# LcsNodes-Main-Controller-Board-A_02_04.net
KiCad netlist of a schematic drawn in EasyEDA
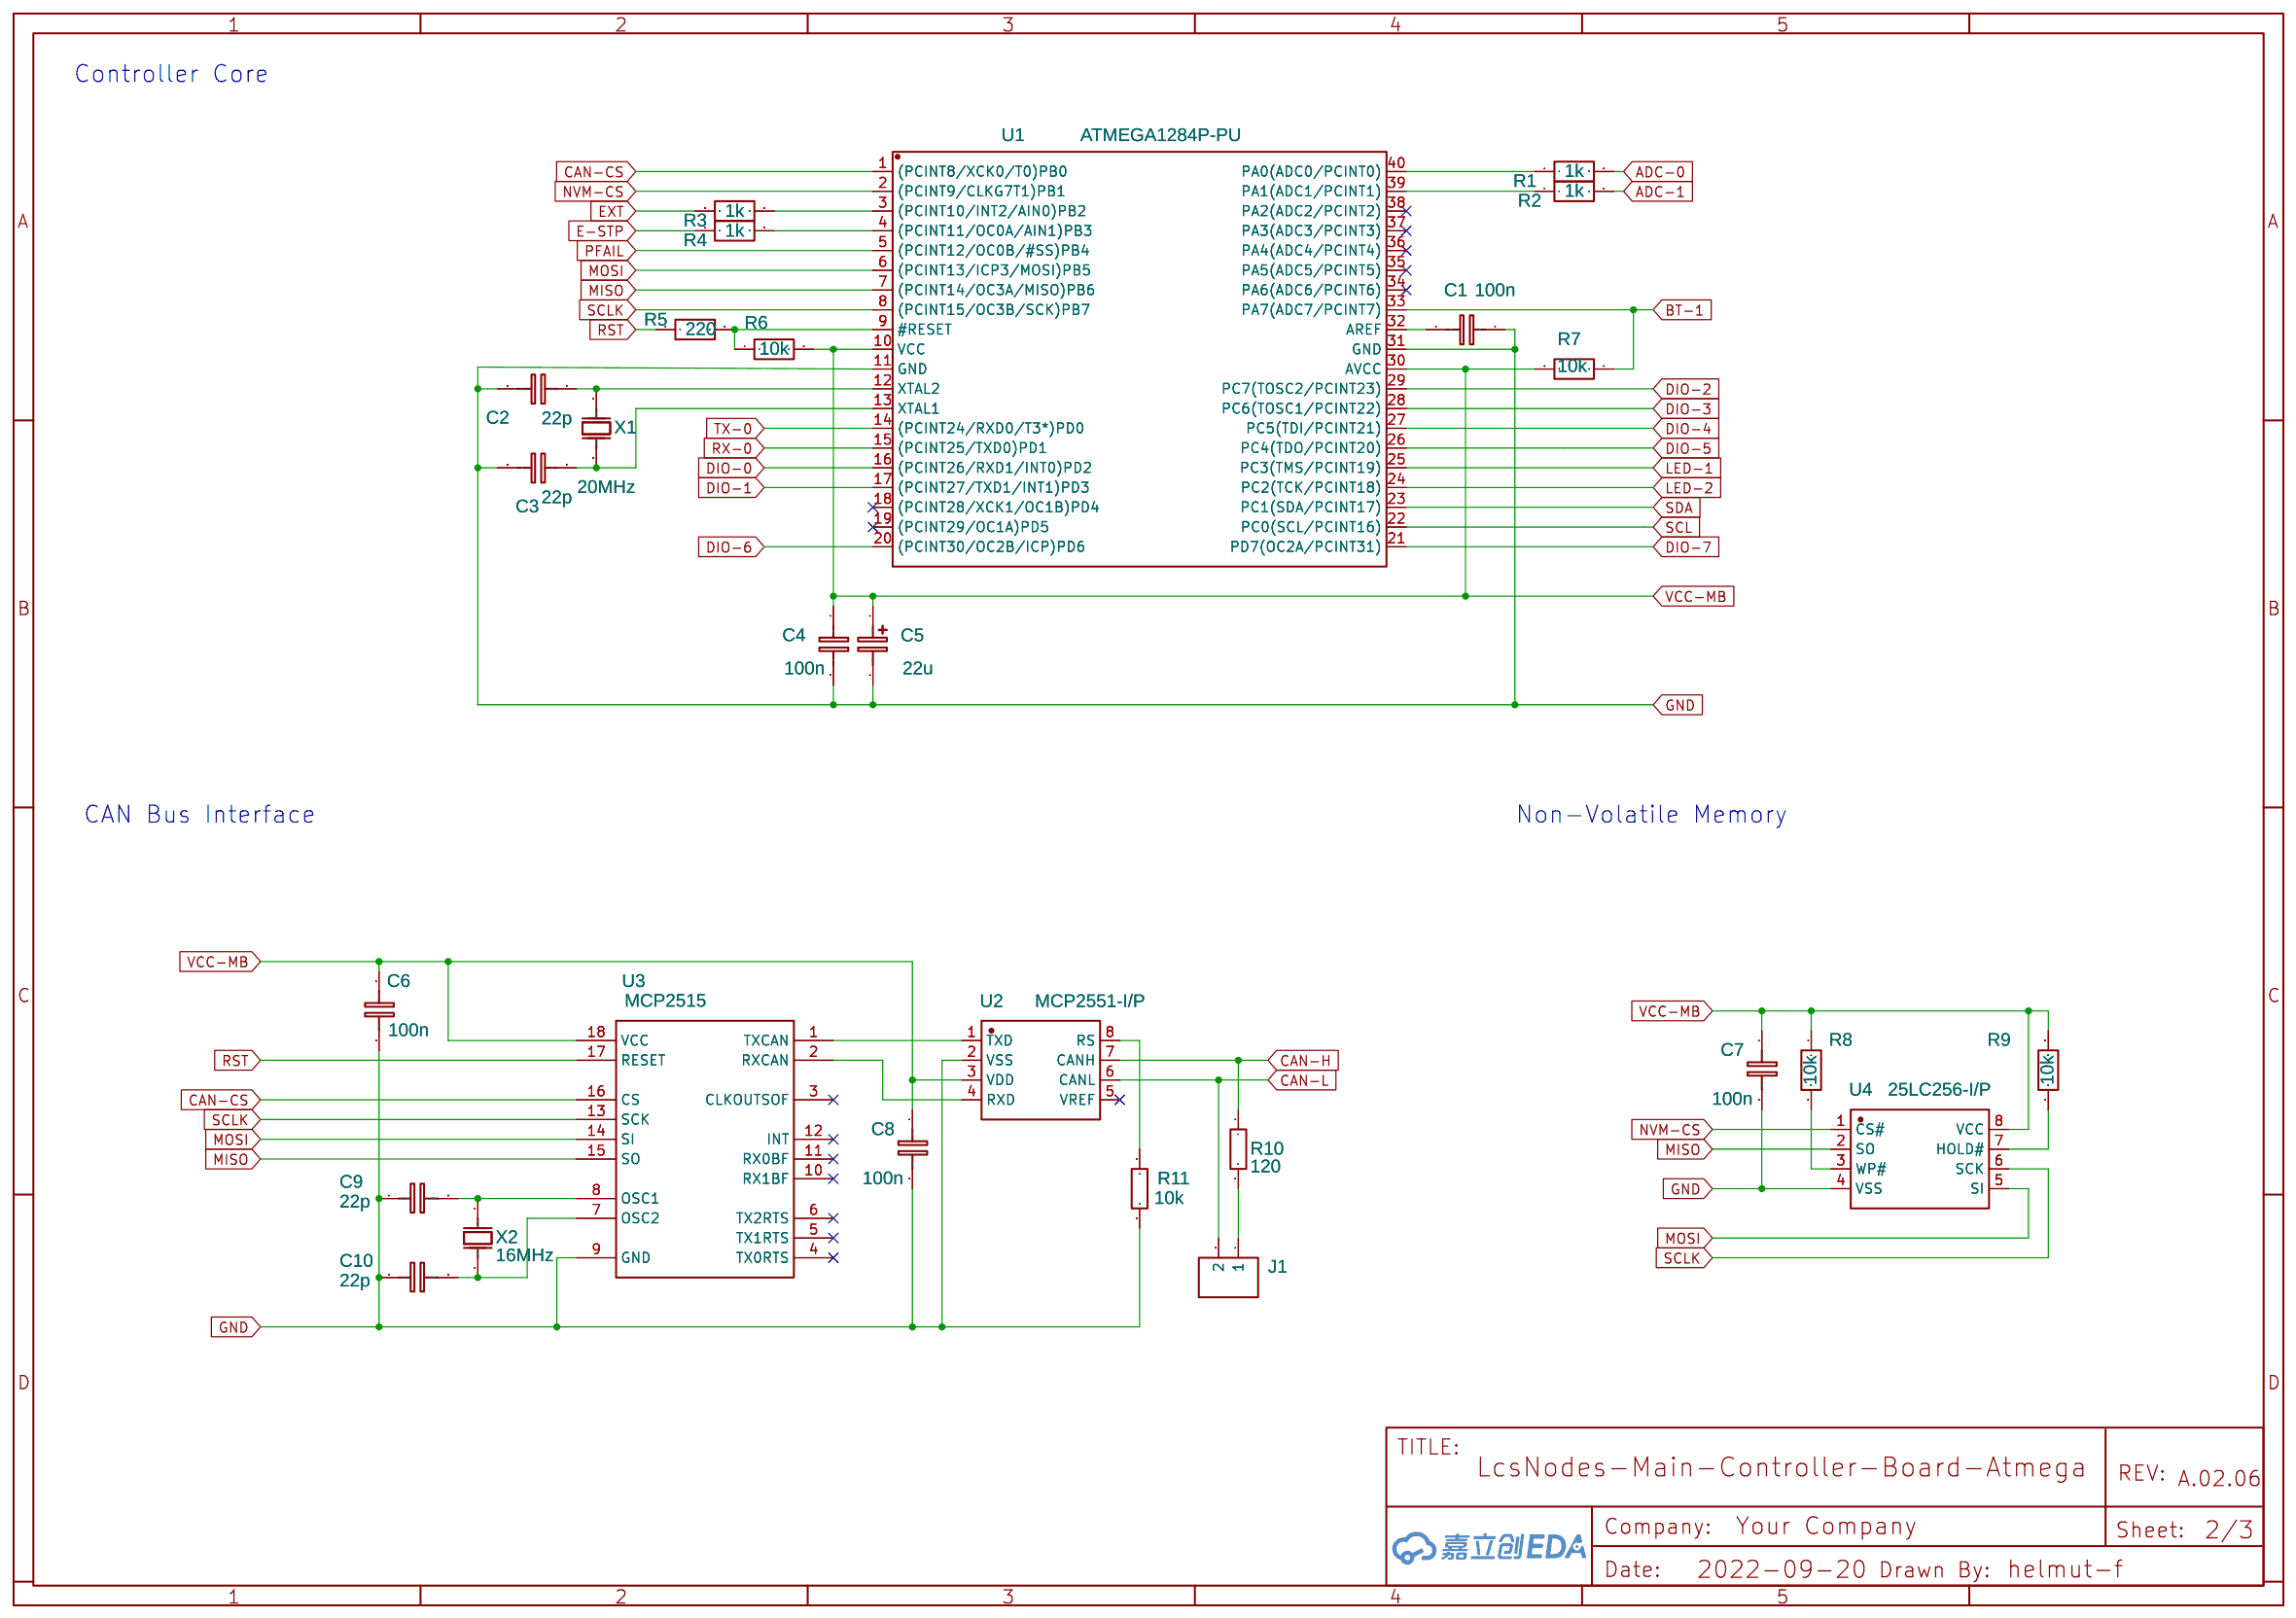
[diagram p0: Controller, CAN, NVM]
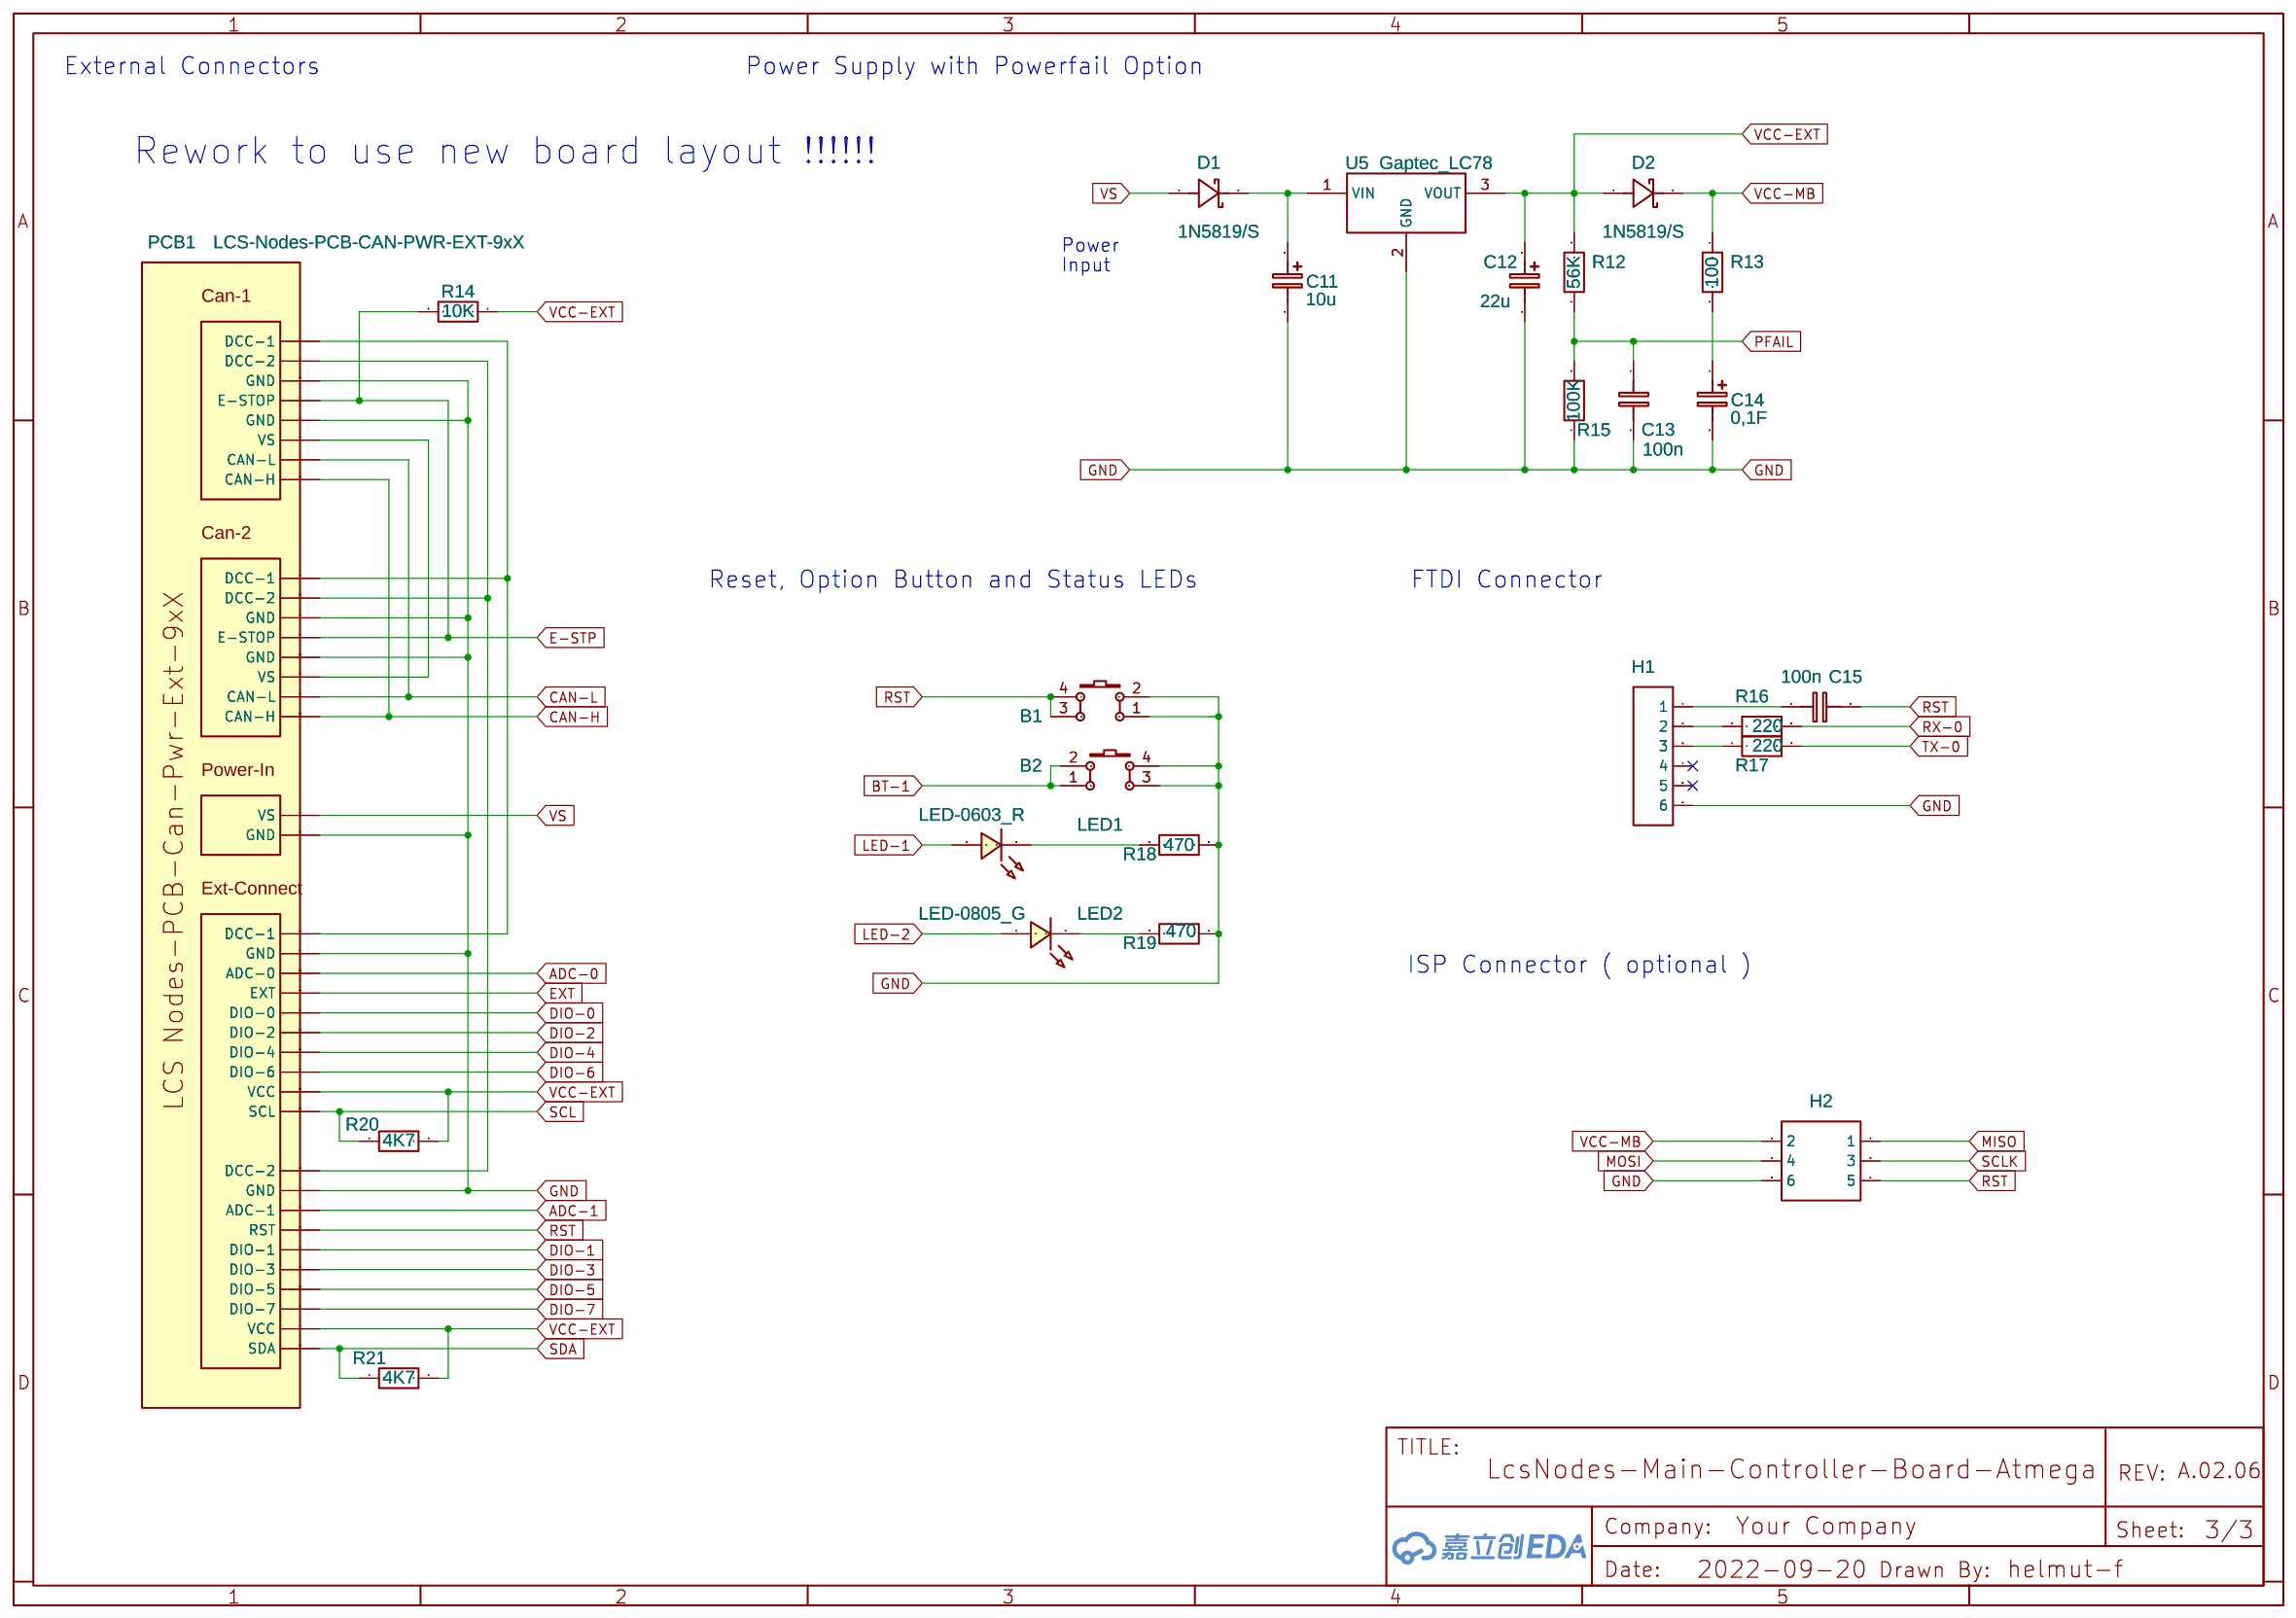
[diagram p1: Connector LCS, FTDI, ISP, Power Supply]
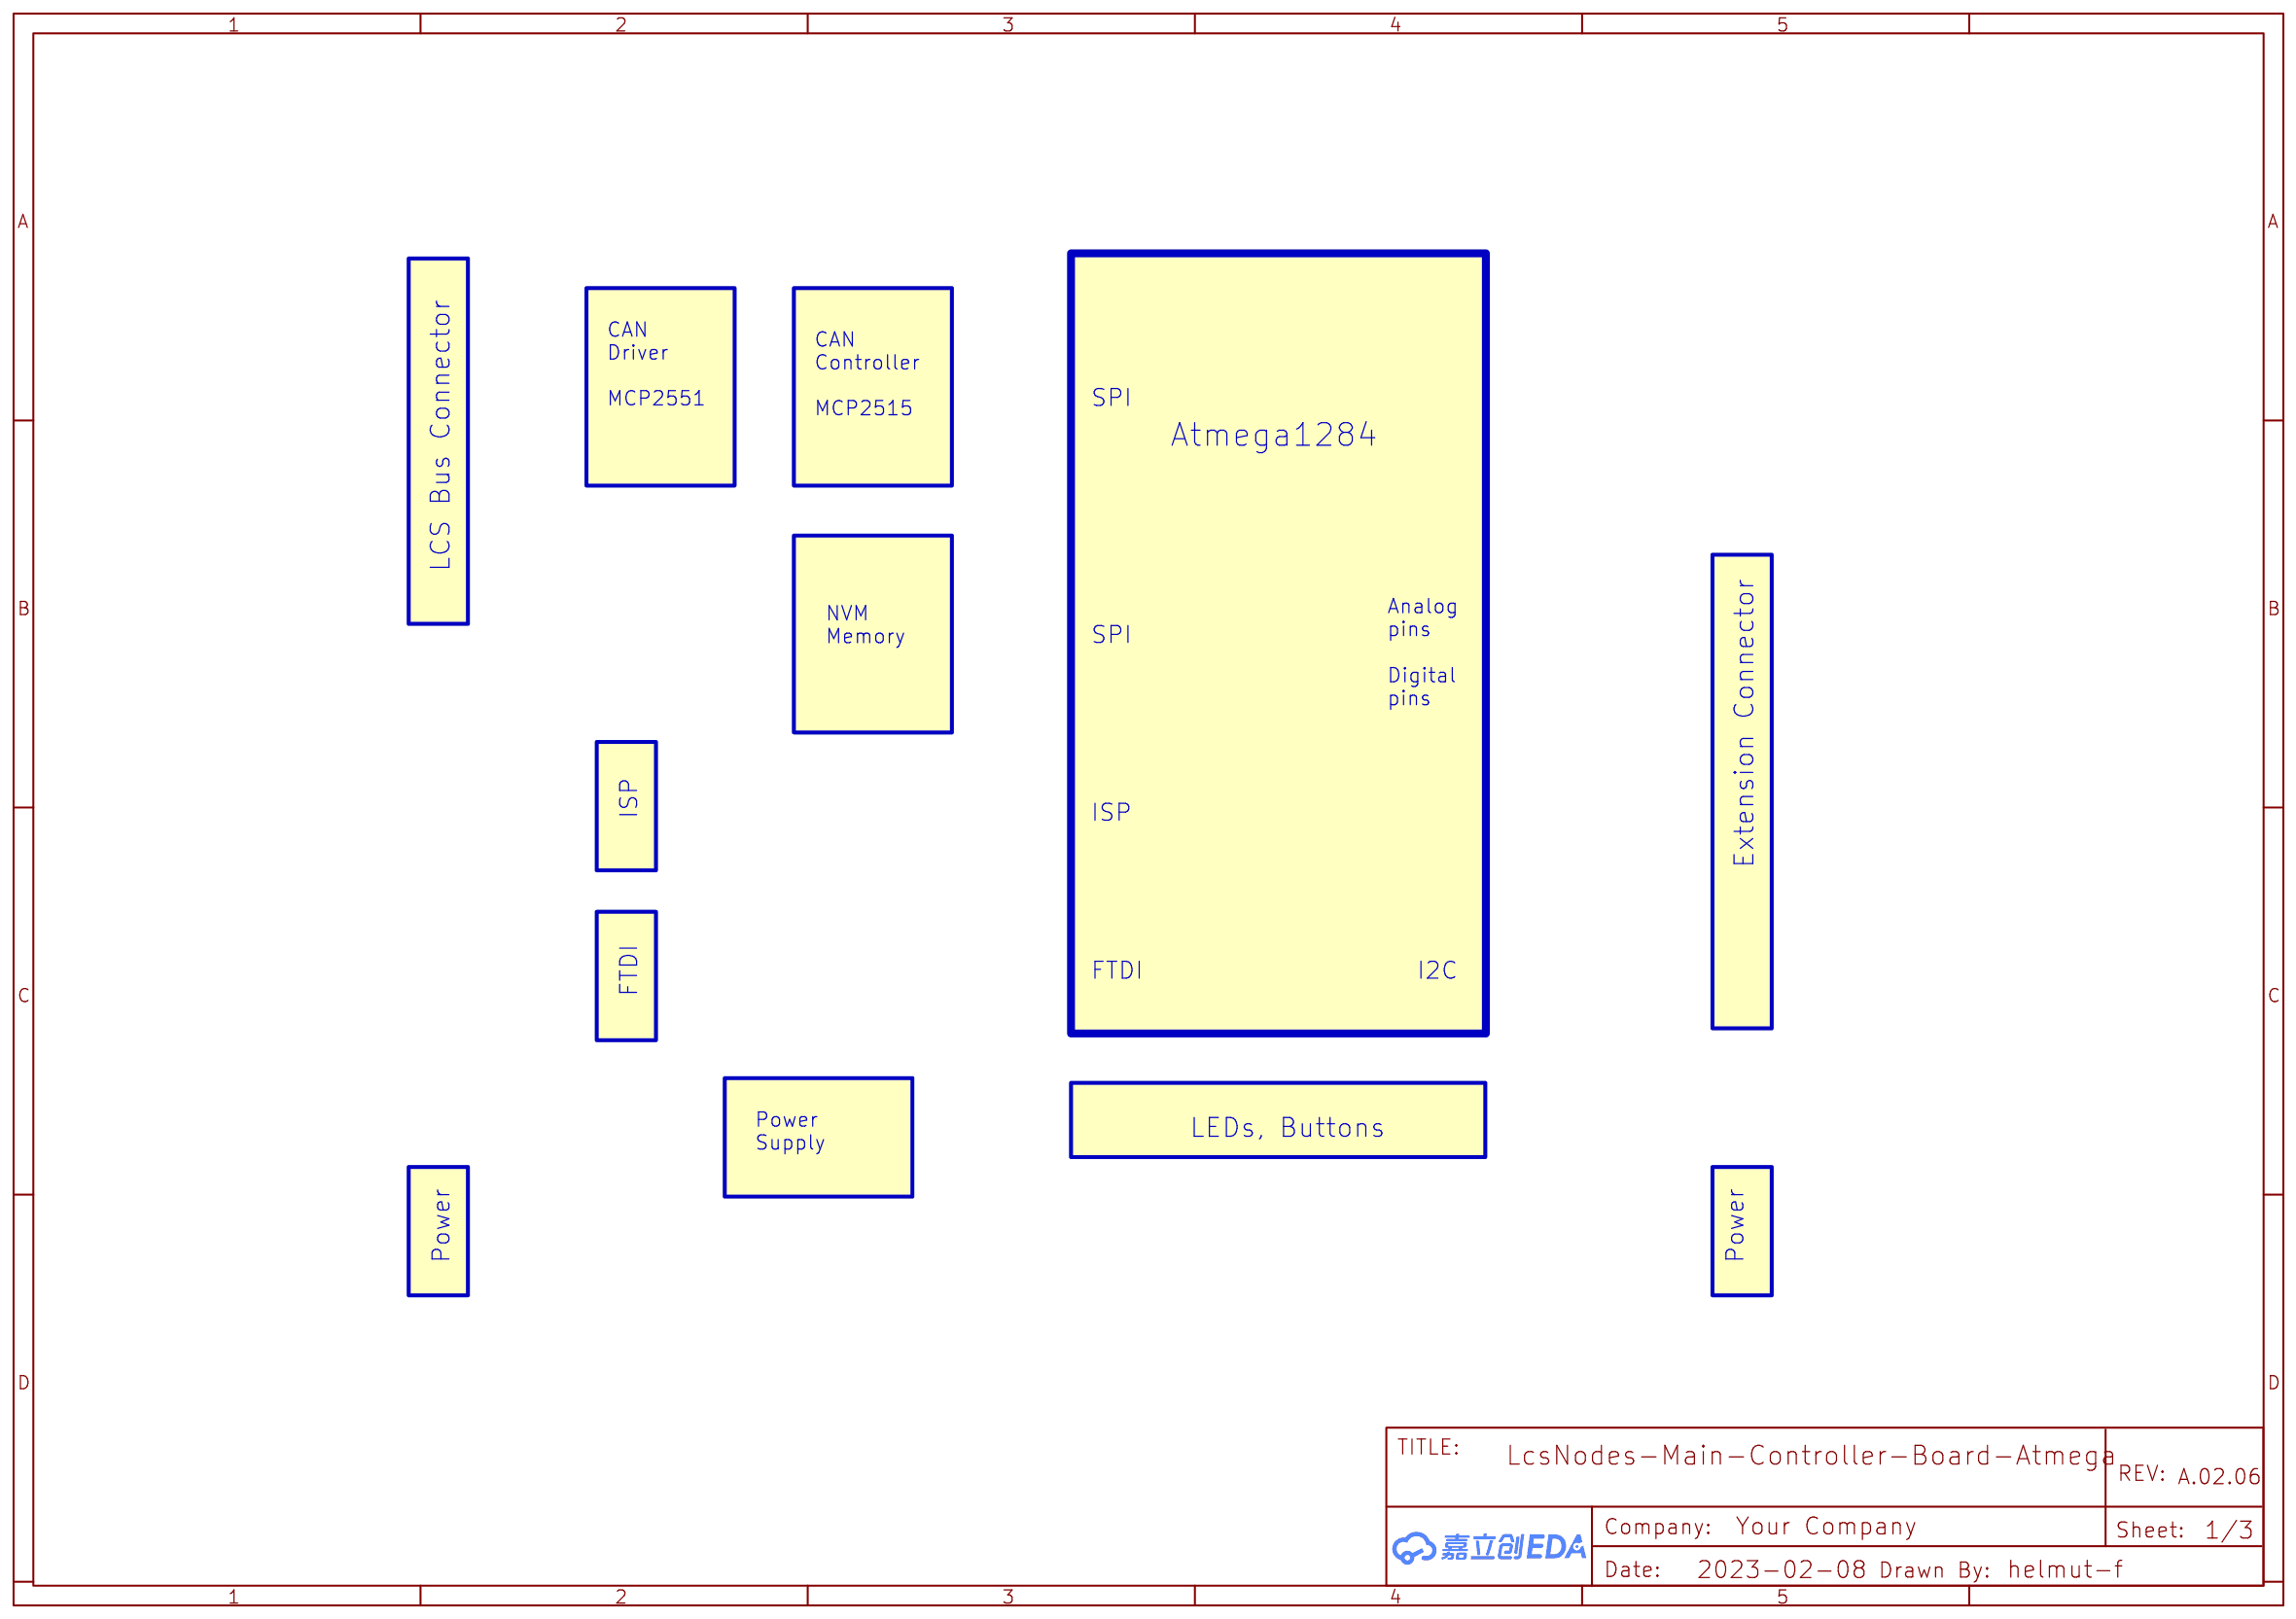
[diagram p2: Block Diagram]

(export (version "E")
  (design (tool "Eeschema 10.0.6"))
  (components
    (comp (ref "C1") (value "100n") (libsource (lib "") (part "C_RAD-0.1_EU")))
    (comp (ref "C2") (value "22p") (libsource (lib "") (part "C_0603_EU_2")))
    (comp (ref "C3") (value "22p") (libsource (lib "") (part "C_0603_EU_2")))
    (comp (ref "C4") (value "100n") (libsource (lib "") (part "C_0603_EU")))
    (comp (ref "C5") (value "22u") (libsource (lib "") (part "CE_TH_D4.0×F1.5_EU")))
    (comp (ref "C6") (value "100n") (libsource (lib "") (part "C_0603_EU")))
    (comp (ref "C7") (value "100n") (libsource (lib "") (part "C_0603_EU_1")))
    (comp (ref "C8") (value "100n") (libsource (lib "") (part "C_0603_EU")))
    (comp (ref "C9") (value "22p") (libsource (lib "") (part "C_0603_EU_3")))
    (comp (ref "C10") (value "22p") (libsource (lib "") (part "C_0603_EU_3")))
    (comp (ref "J1")
      (value "HDR-M-2.54_1x2")
      (fields (field (name "BOM_Supplier Part") "C124375"))
      (libsource (lib "") (part "HDR-M-2.54_1x2"))
    )
    (comp (ref "R1") (value "1k") (libsource (lib "") (part "R_AXIAL-0.3_EU_1")))
    (comp (ref "R2") (value "1k") (libsource (lib "") (part "R_AXIAL-0.3_EU_1")))
    (comp (ref "R3") (value "1k") (libsource (lib "") (part "R_AXIAL-0.3_EU_1")))
    (comp (ref "R4") (value "1k") (libsource (lib "") (part "R_AXIAL-0.3_EU_1")))
    (comp (ref "R5") (value "220") (libsource (lib "") (part "R_AXIAL-0.3_EU_1")))
    (comp (ref "R6") (value "10k") (libsource (lib "") (part "R_AXIAL-0.3_EU_1")))
    (comp (ref "R7") (value "10k") (libsource (lib "") (part "R_AXIAL-0.3_EU")))
    (comp (ref "R8") (value "10k") (libsource (lib "") (part "R_AXIAL-0.3_EU_3")))
    (comp (ref "R9") (value "10k") (libsource (lib "") (part "R_AXIAL-0.3_EU_2")))
    (comp (ref "R10") (value "120") (libsource (lib "") (part "RESISTOR-AXIAL-0.1")))
    (comp (ref "R11") (value "10k") (libsource (lib "") (part "RESISTOR-AXIAL-0.1")))
    (comp (ref "U1")
      (value "ATMEGA1284P-PU")
      (fields (field (name "BOM_Supplier Part") "C116839"))
      (libsource (lib "") (part "ATMEGA1284P-PU"))
    )
    (comp (ref "U2")
      (value "MCP2551-I/P")
      (fields (field (name "BOM_Supplier Part") "C411627"))
      (libsource (lib "") (part "MCP2551-I/P"))
    )
    (comp (ref "U3") (value "MCP2515") (libsource (lib "") (part "MCP2515")))
    (comp (ref "U4")
      (value "25LC256-I/P")
      (fields (field (name "BOM_Supplier Part") "C511271"))
      (libsource (lib "") (part "25LC256-I/P"))
    )
    (comp (ref "X1")
      (value "20MHz")
      (fields
        (field (name "BOM_Manufacturer Part") "X49SM16MSD2SI")
        (field (name "BOM_Supplier Part") "C90678")
      )
      (libsource (lib "") (part "X49SM16MSD2SI"))
    )
    (comp (ref "X2")
      (value "16MHz")
      (fields
        (field (name "BOM_Manufacturer Part") "X49SM16MSD2SI")
        (field (name "BOM_Supplier Part") "C90678")
      )
      (libsource (lib "") (part "X49SM16MSD2SI"))
    )
    (comp (ref "B1")
      (value "Reset")
      (fields
        (field (name "BOM_Manufacturer Part") "K2-1102DP-E4SW-04")
        (field (name "BOM_Supplier Part") "C136684")
      )
      (libsource (lib "") (part "K4-6×6_TH_1"))
    )
    (comp (ref "B2")
      (value "Opt")
      (fields
        (field (name "BOM_Manufacturer Part") "K2-1102DP-E4SW-04")
        (field (name "BOM_Supplier Part") "C136684")
      )
      (libsource (lib "") (part "K4-6×6_TH"))
    )
    (comp (ref "C11") (value "10u") (libsource (lib "") (part "CE_SMD_D5.0×H5.5_EU")))
    (comp (ref "C12") (value "22u") (libsource (lib "") (part "CE_SMD_D5.0×H5.5_EU")))
    (comp (ref "C13") (value "100n") (libsource (lib "") (part "C_RAD-0.2_EU")))
    (comp (ref "C14") (value "0,1F") (libsource (lib "") (part "C_Tan_SMD_A_EU")))
    (comp (ref "C15") (value "100n") (libsource (lib "") (part "C_0603_EU")))
    (comp (ref "D1")
      (value "1N5819/S")
      (fields (field (name "BOM_Supplier Part") "C9900003833"))
      (libsource (lib "") (part "1N5819/S"))
    )
    (comp (ref "D2")
      (value "1N5819/S")
      (fields (field (name "BOM_Supplier Part") "C9900003833"))
      (libsource (lib "") (part "1N5819/S"))
    )
    (comp (ref "H1")
      (value "HDR-F-2.54_1x6")
      (fields (field (name "BOM_Supplier Part") "C40877"))
      (libsource (lib "") (part "HDR-F-2.54_1x6"))
    )
    (comp (ref "H2")
      (value "HDR-F-2.54_2x3")
      (fields (field (name "BOM_Supplier Part") "C65114"))
      (libsource (lib "") (part "HDR-F-2.54_2x3"))
    )
    (comp (ref "LED1")
      (value "LED-0603_R")
      (fields
        (field (name "BOM_Manufacturer Part") "19-217/R6C-AL1M2VY/3T")
        (field (name "BOM_Supplier Part") "C72044")
      )
      (libsource (lib "") (part "LED-0603_R"))
    )
    (comp (ref "LED2")
      (value "LED-0805_G")
      (fields (field (name "BOM_Manufacturer Part") "NCD0805G1") (field (name "BOM_Supplier Part") "C84260"))
      (libsource (lib "") (part "LED-0805_G"))
    )
    (comp (ref "PCB1")
      (value "LCS-Nodes-PCB-CAN-PWR-EXT-9xX")
      (libsource (lib "") (part "LCS-Nodes-PCB-CAN-PWR-EXT-9xX"))
    )
    (comp (ref "R12") (value "56K") (libsource (lib "") (part "R_AXIAL-0.3_EU_1")))
    (comp (ref "R13") (value "100") (libsource (lib "") (part "R_AXIAL-0.3_EU_3")))
    (comp (ref "R14") (value "10K") (libsource (lib "") (part "R_AXIAL-0.3_EU")))
    (comp (ref "R15") (value "100K") (libsource (lib "") (part "R_AXIAL-0.3_EU_1")))
    (comp (ref "R16") (value "220") (libsource (lib "") (part "R_AXIAL-0.3_EU_2")))
    (comp (ref "R17") (value "220") (libsource (lib "") (part "R_AXIAL-0.3_EU_2")))
    (comp (ref "R18") (value "470") (libsource (lib "") (part "R_0805_EU")))
    (comp (ref "R19") (value "470") (libsource (lib "") (part "R_0805_EU")))
    (comp (ref "R20") (value "4K7") (libsource (lib "") (part "R_AXIAL-0.3_EU_2")))
    (comp (ref "R21") (value "4K7") (libsource (lib "") (part "R_AXIAL-0.3_EU_2")))
    (comp (ref "U5") (value "Gaptec_LC78") (libsource (lib "") (part "Gaptec_LC78")))
  )
  (nets
    (net (code "1") (name "ADC-0") (class "Default")
      (node (ref "PCB1") (pin "32") (pinfunction "ADC-0_32") (pintype "unspecified"))
      (node (ref "R1") (pin "2") (pinfunction "2_2") (pintype "unspecified"))
    )
    (net (code "2") (name "ADC-1") (class "Default")
      (node (ref "PCB1") (pin "42") (pinfunction "ADC-1_42") (pintype "unspecified"))
      (node (ref "R2") (pin "2") (pinfunction "2_2") (pintype "unspecified"))
    )
    (net (code "3") (name "BT-1") (class "Default")
      (node (ref "B2") (pin "1") (pinfunction "1_1") (pintype "unspecified"))
      (node (ref "B2") (pin "2") (pinfunction "2_2") (pintype "unspecified"))
      (node (ref "R7") (pin "1") (pinfunction "1_1") (pintype "unspecified"))
      (node (ref "U1") (pin "33") (pinfunction "PA7(ADC7/PCINT7)_33") (pintype "unspecified"))
    )
    (net (code "4") (name "CAN-CS") (class "Default")
      (node (ref "U1") (pin "1") (pinfunction "(PCINT8/XCK0/T0)PB0_1") (pintype "unspecified"))
      (node (ref "U3") (pin "16") (pinfunction "CS_16") (pintype "unspecified"))
    )
    (net (code "5") (name "CAN-H") (class "Default")
      (node (ref "PCB1") (pin "18") (pinfunction "CAN-H_18") (pintype "unspecified"))
      (node (ref "PCB1") (pin "8") (pinfunction "CAN-H_8") (pintype "unspecified"))
      (node (ref "R10") (pin "1") (pinfunction "1_1") (pintype "input"))
      (node (ref "U2") (pin "7") (pinfunction "CANH_7") (pintype "unspecified"))
    )
    (net (code "6") (name "CAN-L") (class "Default")
      (node (ref "J1") (pin "2") (pinfunction "2_2") (pintype "unspecified"))
      (node (ref "PCB1") (pin "17") (pinfunction "CAN-L_17") (pintype "unspecified"))
      (node (ref "PCB1") (pin "7") (pinfunction "CAN-L_7") (pintype "unspecified"))
      (node (ref "U2") (pin "6") (pinfunction "CANL_6") (pintype "unspecified"))
    )
    (net (code "7") (name "DIO-0") (class "Default")
      (node (ref "PCB1") (pin "34") (pinfunction "DIO-0_34") (pintype "unspecified"))
      (node (ref "U1") (pin "16") (pinfunction "(PCINT26/RXD1/INT0)PD2_16") (pintype "unspecified"))
    )
    (net (code "8") (name "DIO-1") (class "Default")
      (node (ref "PCB1") (pin "44") (pinfunction "DIO-1_44") (pintype "unspecified"))
      (node (ref "U1") (pin "17") (pinfunction "(PCINT27/TXD1/INT1)PD3_17") (pintype "unspecified"))
    )
    (net (code "9") (name "DIO-2") (class "Default")
      (node (ref "PCB1") (pin "35") (pinfunction "DIO-2_35") (pintype "unspecified"))
      (node (ref "U1") (pin "29") (pinfunction "PC7(TOSC2/PCINT23)_29") (pintype "unspecified"))
    )
    (net (code "10") (name "DIO-3") (class "Default")
      (node (ref "PCB1") (pin "45") (pinfunction "DIO-3_45") (pintype "unspecified"))
      (node (ref "U1") (pin "28") (pinfunction "PC6(TOSC1/PCINT22)_28") (pintype "unspecified"))
    )
    (net (code "11") (name "DIO-4") (class "Default")
      (node (ref "PCB1") (pin "36") (pinfunction "DIO-4_36") (pintype "unspecified"))
      (node (ref "U1") (pin "27") (pinfunction "PC5(TDI/PCINT21)_27") (pintype "unspecified"))
    )
    (net (code "12") (name "DIO-5") (class "Default")
      (node (ref "PCB1") (pin "46") (pinfunction "DIO-5_46") (pintype "unspecified"))
      (node (ref "U1") (pin "26") (pinfunction "PC4(TDO/PCINT20)_26") (pintype "unspecified"))
    )
    (net (code "13") (name "DIO-6") (class "Default")
      (node (ref "PCB1") (pin "37") (pinfunction "DIO-6_37") (pintype "unspecified"))
      (node (ref "U1") (pin "20") (pinfunction "(PCINT30/OC2B/ICP)PD6_20") (pintype "unspecified"))
    )
    (net (code "14") (name "DIO-7") (class "Default")
      (node (ref "PCB1") (pin "47") (pinfunction "DIO-7_47") (pintype "unspecified"))
      (node (ref "U1") (pin "21") (pinfunction "PD7(OC2A/PCINT31)_21") (pintype "unspecified"))
    )
    (net (code "15") (name "E-STP") (class "Default")
      (node (ref "PCB1") (pin "14") (pinfunction "E-STOP_14") (pintype "unspecified"))
      (node (ref "PCB1") (pin "4") (pinfunction "E-STOP_4") (pintype "unspecified"))
      (node (ref "R14") (pin "2") (pinfunction "2_2") (pintype "unspecified"))
      (node (ref "R4") (pin "1") (pinfunction "1_1") (pintype "unspecified"))
    )
    (net (code "16") (name "EXT") (class "Default")
      (node (ref "PCB1") (pin "33") (pinfunction "EXT_33") (pintype "unspecified"))
      (node (ref "R3") (pin "1") (pinfunction "1_1") (pintype "unspecified"))
    )
    (net (code "17") (name "GND") (class "Default")
      (node (ref "B1") (pin "1") (pinfunction "1_1") (pintype "unspecified"))
      (node (ref "B1") (pin "2") (pinfunction "2_2") (pintype "unspecified"))
      (node (ref "B2") (pin "3") (pinfunction "3_3") (pintype "unspecified"))
      (node (ref "B2") (pin "4") (pinfunction "4_4") (pintype "unspecified"))
      (node (ref "C1") (pin "1") (pinfunction "1_1") (pintype "unspecified"))
      (node (ref "C10") (pin "1") (pinfunction "1_1") (pintype "unspecified"))
      (node (ref "C11") (pin "2") (pinfunction "2_2") (pintype "unspecified"))
      (node (ref "C12") (pin "2") (pinfunction "2_2") (pintype "unspecified"))
      (node (ref "C13") (pin "2") (pinfunction "2_2") (pintype "unspecified"))
      (node (ref "C14") (pin "2") (pinfunction "2_2") (pintype "unspecified"))
      (node (ref "C2") (pin "2") (pinfunction "2_2") (pintype "unspecified"))
      (node (ref "C3") (pin "2") (pinfunction "2_2") (pintype "unspecified"))
      (node (ref "C4") (pin "2") (pinfunction "2_2") (pintype "unspecified"))
      (node (ref "C5") (pin "2") (pinfunction "2_2") (pintype "unspecified"))
      (node (ref "C6") (pin "2") (pinfunction "2_2") (pintype "unspecified"))
      (node (ref "C7") (pin "2") (pinfunction "2_2") (pintype "unspecified"))
      (node (ref "C8") (pin "2") (pinfunction "2_2") (pintype "unspecified"))
      (node (ref "C9") (pin "1") (pinfunction "1_1") (pintype "unspecified"))
      (node (ref "H1") (pin "6") (pinfunction "6_6") (pintype "input"))
      (node (ref "H2") (pin "6") (pinfunction "6_6") (pintype "input"))
      (node (ref "PCB1") (pin "13") (pinfunction "GND_13") (pintype "unspecified"))
      (node (ref "PCB1") (pin "15") (pinfunction "GND_15") (pintype "unspecified"))
      (node (ref "PCB1") (pin "21") (pinfunction "GND_21") (pintype "unspecified"))
      (node (ref "PCB1") (pin "3") (pinfunction "GND_3") (pintype "unspecified"))
      (node (ref "PCB1") (pin "31") (pinfunction "GND_31") (pintype "unspecified"))
      (node (ref "PCB1") (pin "41") (pinfunction "GND_41") (pintype "unspecified"))
      (node (ref "PCB1") (pin "5") (pinfunction "GND_5") (pintype "unspecified"))
      (node (ref "R11") (pin "2") (pinfunction "2_2") (pintype "input"))
      (node (ref "R15") (pin "1") (pinfunction "1_1") (pintype "unspecified"))
      (node (ref "R18") (pin "1") (pinfunction "1_1") (pintype "unspecified"))
      (node (ref "R19") (pin "1") (pinfunction "1_1") (pintype "unspecified"))
      (node (ref "U1") (pin "11") (pinfunction "GND_11") (pintype "unspecified"))
      (node (ref "U1") (pin "31") (pinfunction "GND_31") (pintype "unspecified"))
      (node (ref "U2") (pin "2") (pinfunction "VSS_2") (pintype "unspecified"))
      (node (ref "U3") (pin "9") (pinfunction "GND_9") (pintype "passive"))
      (node (ref "U4") (pin "4") (pinfunction "VSS_4") (pintype "unspecified"))
      (node (ref "U5") (pin "2") (pinfunction "GND_2") (pintype "unspecified"))
    )
    (net (code "18") (name "LED-1") (class "Default")
      (node (ref "LED1") (pin "1") (pinfunction "1_1") (pintype "unspecified"))
      (node (ref "U1") (pin "25") (pinfunction "PC3(TMS/PCINT19)_25") (pintype "unspecified"))
    )
    (net (code "19") (name "LED-2") (class "Default")
      (node (ref "LED2") (pin "1") (pinfunction "1_1") (pintype "unspecified"))
      (node (ref "U1") (pin "24") (pinfunction "PC2(TCK/PCINT18)_24") (pintype "unspecified"))
    )
    (net (code "20") (name "MISO") (class "Default")
      (node (ref "H2") (pin "1") (pinfunction "1_1") (pintype "input"))
      (node (ref "U1") (pin "7") (pinfunction "(PCINT14/OC3A/MISO)PB6_7") (pintype "unspecified"))
      (node (ref "U3") (pin "15") (pinfunction "SO_15") (pintype "output"))
      (node (ref "U4") (pin "2") (pinfunction "SO_2") (pintype "unspecified"))
    )
    (net (code "21") (name "MOSI") (class "Default")
      (node (ref "H2") (pin "4") (pinfunction "4_4") (pintype "input"))
      (node (ref "U1") (pin "6") (pinfunction "(PCINT13/ICP3/MOSI)PB5_6") (pintype "unspecified"))
      (node (ref "U3") (pin "14") (pinfunction "SI_14") (pintype "unspecified"))
      (node (ref "U4") (pin "5") (pinfunction "SI_5") (pintype "unspecified"))
    )
    (net (code "22") (name "NVM-CS") (class "Default")
      (node (ref "U1") (pin "2") (pinfunction "(PCINT9/CLKG7T1)PB1_2") (pintype "unspecified"))
      (node (ref "U4") (pin "1") (pinfunction "CS#_1") (pintype "unspecified"))
    )
    (net (code "23") (name "Net-(C14-Pad1)") (class "Default")
      (node (ref "C14") (pin "1") (pinfunction "1_1") (pintype "unspecified"))
      (node (ref "R13") (pin "2") (pinfunction "2_2") (pintype "unspecified"))
    )
    (net (code "24") (name "Net-(C15-Pad1)") (class "Default")
      (node (ref "C15") (pin "1") (pinfunction "1_1") (pintype "unspecified"))
      (node (ref "H1") (pin "1") (pinfunction "1_1") (pintype "input"))
    )
    (net (code "25") (name "Net-(D1-K)") (class "Default")
      (node (ref "C11") (pin "1") (pinfunction "1_1") (pintype "unspecified"))
      (node (ref "D1") (pin "2") (pinfunction "K_2") (pintype "unspecified"))
      (node (ref "U5") (pin "1") (pinfunction "VIN_1") (pintype "unspecified"))
    )
    (net (code "26") (name "Net-(H1-Pad2)") (class "Default")
      (node (ref "H1") (pin "2") (pinfunction "2_2") (pintype "input"))
      (node (ref "R16") (pin "1") (pinfunction "1_1") (pintype "unspecified"))
    )
    (net (code "27") (name "Net-(H1-Pad3)") (class "Default")
      (node (ref "H1") (pin "3") (pinfunction "3_3") (pintype "input"))
      (node (ref "R17") (pin "1") (pinfunction "1_1") (pintype "unspecified"))
    )
    (net (code "28") (name "Net-(J1-Pad1)") (class "Default")
      (node (ref "J1") (pin "1") (pinfunction "1_1") (pintype "unspecified"))
      (node (ref "R10") (pin "2") (pinfunction "2_2") (pintype "input"))
    )
    (net (code "29") (name "Net-(LED1-Pad2)") (class "Default")
      (node (ref "LED1") (pin "2") (pinfunction "2_2") (pintype "unspecified"))
      (node (ref "R18") (pin "2") (pinfunction "2_2") (pintype "unspecified"))
    )
    (net (code "30") (name "Net-(LED2-Pad2)") (class "Default")
      (node (ref "LED2") (pin "2") (pinfunction "2_2") (pintype "unspecified"))
      (node (ref "R19") (pin "2") (pinfunction "2_2") (pintype "unspecified"))
    )
    (net (code "31") (name "Net-(PCB1-DCC-1-Pad1)") (class "Default")
      (node (ref "PCB1") (pin "1") (pinfunction "DCC-1_1") (pintype "unspecified"))
      (node (ref "PCB1") (pin "11") (pinfunction "DCC-1_11") (pintype "unspecified"))
      (node (ref "PCB1") (pin "30") (pinfunction "DCC-1_30") (pintype "unspecified"))
    )
    (net (code "32") (name "Net-(PCB1-DCC-2-Pad12)") (class "Default")
      (node (ref "PCB1") (pin "12") (pinfunction "DCC-2_12") (pintype "unspecified"))
      (node (ref "PCB1") (pin "2") (pinfunction "DCC-2_2") (pintype "unspecified"))
      (node (ref "PCB1") (pin "40") (pinfunction "DCC-2_40") (pintype "unspecified"))
    )
    (net (code "33") (name "Net-(PCB1-VS-Pad16)") (class "Default")
      (node (ref "PCB1") (pin "16") (pinfunction "VS_16") (pintype "unspecified"))
      (node (ref "PCB1") (pin "6") (pinfunction "VS_6") (pintype "unspecified"))
    )
    (net (code "34") (name "Net-(U1-#RESET)") (class "Default")
      (node (ref "R5") (pin "2") (pinfunction "2_2") (pintype "unspecified"))
      (node (ref "R6") (pin "1") (pinfunction "1_1") (pintype "unspecified"))
      (node (ref "U1") (pin "9") (pinfunction "#RESET_9") (pintype "unspecified"))
    )
    (net (code "35") (name "Net-(U1-(PCINT10{slash}INT2{slash}AIN0)PB2)") (class "Default")
      (node (ref "R3") (pin "2") (pinfunction "2_2") (pintype "unspecified"))
      (node (ref "U1") (pin "3") (pinfunction "(PCINT10/INT2/AIN0)PB2_3") (pintype "unspecified"))
    )
    (net (code "36") (name "Net-(U1-(PCINT11{slash}OC0A{slash}AIN1)PB3)") (class "Default")
      (node (ref "R4") (pin "2") (pinfunction "2_2") (pintype "unspecified"))
      (node (ref "U1") (pin "4") (pinfunction "(PCINT11/OC0A/AIN1)PB3_4") (pintype "unspecified"))
    )
    (net (code "37") (name "Net-(U1-AREF)") (class "Default")
      (node (ref "C1") (pin "2") (pinfunction "2_2") (pintype "unspecified"))
      (node (ref "U1") (pin "32") (pinfunction "AREF_32") (pintype "unspecified"))
    )
    (net (code "38") (name "Net-(U1-PA0(ADC0{slash}PCINT0))") (class "Default")
      (node (ref "R1") (pin "1") (pinfunction "1_1") (pintype "unspecified"))
      (node (ref "U1") (pin "40") (pinfunction "PA0(ADC0/PCINT0)_40") (pintype "unspecified"))
    )
    (net (code "39") (name "Net-(U1-PA1(ADC1{slash}PCINT1))") (class "Default")
      (node (ref "R2") (pin "1") (pinfunction "1_1") (pintype "unspecified"))
      (node (ref "U1") (pin "39") (pinfunction "PA1(ADC1/PCINT1)_39") (pintype "unspecified"))
    )
    (net (code "40") (name "Net-(U1-XTAL1)") (class "Default")
      (node (ref "C3") (pin "1") (pinfunction "1_1") (pintype "unspecified"))
      (node (ref "U1") (pin "13") (pinfunction "XTAL1_13") (pintype "unspecified"))
      (node (ref "X1") (pin "2") (pinfunction "OSC2_2") (pintype "input"))
    )
    (net (code "41") (name "Net-(U1-XTAL2)") (class "Default")
      (node (ref "C2") (pin "1") (pinfunction "1_1") (pintype "unspecified"))
      (node (ref "U1") (pin "12") (pinfunction "XTAL2_12") (pintype "unspecified"))
      (node (ref "X1") (pin "1") (pinfunction "OSC1_1") (pintype "input"))
    )
    (net (code "42") (name "Net-(U2-RS)") (class "Default")
      (node (ref "R11") (pin "1") (pinfunction "1_1") (pintype "input"))
      (node (ref "U2") (pin "8") (pinfunction "RS_8") (pintype "unspecified"))
    )
    (net (code "43") (name "Net-(U2-RXD)") (class "Default")
      (node (ref "U2") (pin "4") (pinfunction "RXD_4") (pintype "unspecified"))
      (node (ref "U3") (pin "2") (pinfunction "RXCAN_2") (pintype "unspecified"))
    )
    (net (code "44") (name "Net-(U2-TXD)") (class "Default")
      (node (ref "U2") (pin "1") (pinfunction "TXD_1") (pintype "unspecified"))
      (node (ref "U3") (pin "1") (pinfunction "TXCAN_1") (pintype "output"))
    )
    (net (code "45") (name "Net-(U3-OSC1)") (class "Default")
      (node (ref "C9") (pin "2") (pinfunction "2_2") (pintype "unspecified"))
      (node (ref "U3") (pin "8") (pinfunction "OSC1_8") (pintype "unspecified"))
      (node (ref "X2") (pin "1") (pinfunction "OSC1_1") (pintype "input"))
    )
    (net (code "46") (name "Net-(U3-OSC2)") (class "Default")
      (node (ref "C10") (pin "2") (pinfunction "2_2") (pintype "unspecified"))
      (node (ref "U3") (pin "7") (pinfunction "OSC2_7") (pintype "output"))
      (node (ref "X2") (pin "2") (pinfunction "OSC2_2") (pintype "input"))
    )
    (net (code "47") (name "Net-(U4-HOLD#)") (class "Default")
      (node (ref "R9") (pin "1") (pinfunction "1_1") (pintype "unspecified"))
      (node (ref "U4") (pin "7") (pinfunction "HOLD#_7") (pintype "unspecified"))
    )
    (net (code "48") (name "Net-(U4-WP#)") (class "Default")
      (node (ref "R8") (pin "2") (pinfunction "2_2") (pintype "unspecified"))
      (node (ref "U4") (pin "3") (pinfunction "WP#_3") (pintype "unspecified"))
    )
    (net (code "49") (name "PFAIL") (class "Default")
      (node (ref "C13") (pin "1") (pinfunction "1_1") (pintype "unspecified"))
      (node (ref "R12") (pin "1") (pinfunction "1_1") (pintype "unspecified"))
      (node (ref "R15") (pin "2") (pinfunction "2_2") (pintype "unspecified"))
      (node (ref "U1") (pin "5") (pinfunction "(PCINT12/OC0B/#SS)PB4_5") (pintype "unspecified"))
    )
    (net (code "50") (name "RST") (class "Default")
      (node (ref "B1") (pin "3") (pinfunction "3_3") (pintype "unspecified"))
      (node (ref "B1") (pin "4") (pinfunction "4_4") (pintype "unspecified"))
      (node (ref "C15") (pin "2") (pinfunction "2_2") (pintype "unspecified"))
      (node (ref "H2") (pin "5") (pinfunction "5_5") (pintype "input"))
      (node (ref "PCB1") (pin "43") (pinfunction "RST_43") (pintype "unspecified"))
      (node (ref "R5") (pin "1") (pinfunction "1_1") (pintype "unspecified"))
      (node (ref "U3") (pin "17") (pinfunction "RESET_17") (pintype "unspecified"))
    )
    (net (code "51") (name "RX-0") (class "Default")
      (node (ref "R16") (pin "2") (pinfunction "2_2") (pintype "unspecified"))
      (node (ref "U1") (pin "15") (pinfunction "(PCINT25/TXD0)PD1_15") (pintype "unspecified"))
    )
    (net (code "52") (name "SCL") (class "Default")
      (node (ref "PCB1") (pin "39") (pinfunction "SCL_39") (pintype "unspecified"))
      (node (ref "R20") (pin "1") (pinfunction "1_1") (pintype "unspecified"))
      (node (ref "U1") (pin "22") (pinfunction "PC0(SCL/PCINT16)_22") (pintype "unspecified"))
    )
    (net (code "53") (name "SCLK") (class "Default")
      (node (ref "H2") (pin "3") (pinfunction "3_3") (pintype "input"))
      (node (ref "U1") (pin "8") (pinfunction "(PCINT15/OC3B/SCK)PB7_8") (pintype "unspecified"))
      (node (ref "U3") (pin "13") (pinfunction "SCK_13") (pintype "unspecified"))
      (node (ref "U4") (pin "6") (pinfunction "SCK_6") (pintype "unspecified"))
    )
    (net (code "54") (name "SDA") (class "Default")
      (node (ref "PCB1") (pin "49") (pinfunction "SDA_49") (pintype "unspecified"))
      (node (ref "R21") (pin "1") (pinfunction "1_1") (pintype "unspecified"))
      (node (ref "U1") (pin "23") (pinfunction "PC1(SDA/PCINT17)_23") (pintype "unspecified"))
    )
    (net (code "55") (name "TX-0") (class "Default")
      (node (ref "R17") (pin "2") (pinfunction "2_2") (pintype "unspecified"))
      (node (ref "U1") (pin "14") (pinfunction "(PCINT24/RXD0/T3*)PD0_14") (pintype "unspecified"))
    )
    (net (code "56") (name "VCC-EXT") (class "Default")
      (node (ref "C12") (pin "1") (pinfunction "1_1") (pintype "unspecified"))
      (node (ref "D2") (pin "1") (pinfunction "A_1") (pintype "unspecified"))
      (node (ref "PCB1") (pin "38") (pinfunction "VCC_38") (pintype "unspecified"))
      (node (ref "PCB1") (pin "48") (pinfunction "VCC_48") (pintype "unspecified"))
      (node (ref "R12") (pin "2") (pinfunction "2_2") (pintype "unspecified"))
      (node (ref "R14") (pin "1") (pinfunction "1_1") (pintype "unspecified"))
      (node (ref "R20") (pin "2") (pinfunction "2_2") (pintype "unspecified"))
      (node (ref "R21") (pin "2") (pinfunction "2_2") (pintype "unspecified"))
      (node (ref "U5") (pin "3") (pinfunction "VOUT_3") (pintype "unspecified"))
    )
    (net (code "57") (name "VCC-MB") (class "Default")
      (node (ref "C4") (pin "1") (pinfunction "1_1") (pintype "unspecified"))
      (node (ref "C5") (pin "1") (pinfunction "1_1") (pintype "unspecified"))
      (node (ref "C6") (pin "1") (pinfunction "1_1") (pintype "unspecified"))
      (node (ref "C7") (pin "1") (pinfunction "1_1") (pintype "unspecified"))
      (node (ref "C8") (pin "1") (pinfunction "1_1") (pintype "unspecified"))
      (node (ref "D2") (pin "2") (pinfunction "K_2") (pintype "unspecified"))
      (node (ref "H2") (pin "2") (pinfunction "2_2") (pintype "input"))
      (node (ref "R13") (pin "1") (pinfunction "1_1") (pintype "unspecified"))
      (node (ref "R6") (pin "2") (pinfunction "2_2") (pintype "unspecified"))
      (node (ref "R7") (pin "2") (pinfunction "2_2") (pintype "unspecified"))
      (node (ref "R8") (pin "1") (pinfunction "1_1") (pintype "unspecified"))
      (node (ref "R9") (pin "2") (pinfunction "2_2") (pintype "unspecified"))
      (node (ref "U1") (pin "10") (pinfunction "VCC_10") (pintype "unspecified"))
      (node (ref "U1") (pin "30") (pinfunction "AVCC_30") (pintype "unspecified"))
      (node (ref "U2") (pin "3") (pinfunction "VDD_3") (pintype "unspecified"))
      (node (ref "U3") (pin "18") (pinfunction "VCC_18") (pintype "passive"))
      (node (ref "U4") (pin "8") (pinfunction "VCC_8") (pintype "unspecified"))
    )
    (net (code "58") (name "VS") (class "Default")
      (node (ref "D1") (pin "1") (pinfunction "A_1") (pintype "unspecified"))
      (node (ref "PCB1") (pin "20") (pinfunction "VS_20") (pintype "unspecified"))
    )
    (net (code "59") (name "unconnected-(H1-Pad4)") (class "Default")
      (node (ref "H1") (pin "4") (pinfunction "4_4") (pintype "input+no_connect"))
    )
    (net (code "60") (name "unconnected-(H1-Pad5)") (class "Default")
      (node (ref "H1") (pin "5") (pinfunction "5_5") (pintype "input+no_connect"))
    )
    (net (code "61") (name "unconnected-(U1-(PCINT28{slash}XCK1{slash}OC1B)PD4-Pad18)") (class "Default")
      (node (ref "U1") (pin "18") (pinfunction "(PCINT28/XCK1/OC1B)PD4_18") (pintype "unspecified+no_connect"))
    )
    (net (code "62") (name "unconnected-(U1-(PCINT29{slash}OC1A)PD5-Pad19)") (class "Default")
      (node (ref "U1") (pin "19") (pinfunction "(PCINT29/OC1A)PD5_19") (pintype "unspecified+no_connect"))
    )
    (net (code "63") (name "unconnected-(U1-PA2(ADC2{slash}PCINT2)-Pad38)") (class "Default")
      (node (ref "U1") (pin "38") (pinfunction "PA2(ADC2/PCINT2)_38") (pintype "unspecified+no_connect"))
    )
    (net (code "64") (name "unconnected-(U1-PA3(ADC3{slash}PCINT3)-Pad37)") (class "Default")
      (node (ref "U1") (pin "37") (pinfunction "PA3(ADC3/PCINT3)_37") (pintype "unspecified+no_connect"))
    )
    (net (code "65") (name "unconnected-(U1-PA4(ADC4{slash}PCINT4)-Pad36)") (class "Default")
      (node (ref "U1") (pin "36") (pinfunction "PA4(ADC4/PCINT4)_36") (pintype "unspecified+no_connect"))
    )
    (net (code "66") (name "unconnected-(U1-PA5(ADC5{slash}PCINT5)-Pad35)") (class "Default")
      (node (ref "U1") (pin "35") (pinfunction "PA5(ADC5/PCINT5)_35") (pintype "unspecified+no_connect"))
    )
    (net (code "67") (name "unconnected-(U1-PA6(ADC6{slash}PCINT6)-Pad34)") (class "Default")
      (node (ref "U1") (pin "34") (pinfunction "PA6(ADC6/PCINT6)_34") (pintype "unspecified+no_connect"))
    )
    (net (code "68") (name "unconnected-(U2-VREF-Pad5)") (class "Default")
      (node (ref "U2") (pin "5") (pinfunction "VREF_5") (pintype "unspecified+no_connect"))
    )
    (net (code "69") (name "unconnected-(U3-CLKOUTSOF-Pad3)") (class "Default")
      (node (ref "U3") (pin "3") (pinfunction "CLKOUTSOF_3") (pintype "output+no_connect"))
    )
    (net (code "70") (name "unconnected-(U3-INT-Pad12)") (class "Default")
      (node (ref "U3") (pin "12") (pinfunction "INT_12") (pintype "output+no_connect"))
    )
    (net (code "71") (name "unconnected-(U3-RX0BF-Pad11)") (class "Default")
      (node (ref "U3") (pin "11") (pinfunction "RX0BF_11") (pintype "output+no_connect"))
    )
    (net (code "72") (name "unconnected-(U3-RX1BF-Pad10)") (class "Default")
      (node (ref "U3") (pin "10") (pinfunction "RX1BF_10") (pintype "output+no_connect"))
    )
    (net (code "73") (name "unconnected-(U3-TX0RTS-Pad4)") (class "Default")
      (node (ref "U3") (pin "4") (pinfunction "TX0RTS_4") (pintype "unspecified+no_connect"))
    )
    (net (code "74") (name "unconnected-(U3-TX1RTS-Pad5)") (class "Default")
      (node (ref "U3") (pin "5") (pinfunction "TX1RTS_5") (pintype "unspecified+no_connect"))
    )
    (net (code "75") (name "unconnected-(U3-TX2RTS-Pad6)") (class "Default")
      (node (ref "U3") (pin "6") (pinfunction "TX2RTS_6") (pintype "unspecified+no_connect"))
    )
  )
)
